# Platienen_schalplan_Backup_2.net
KiCad netlist of a schematic drawn in EAGLE
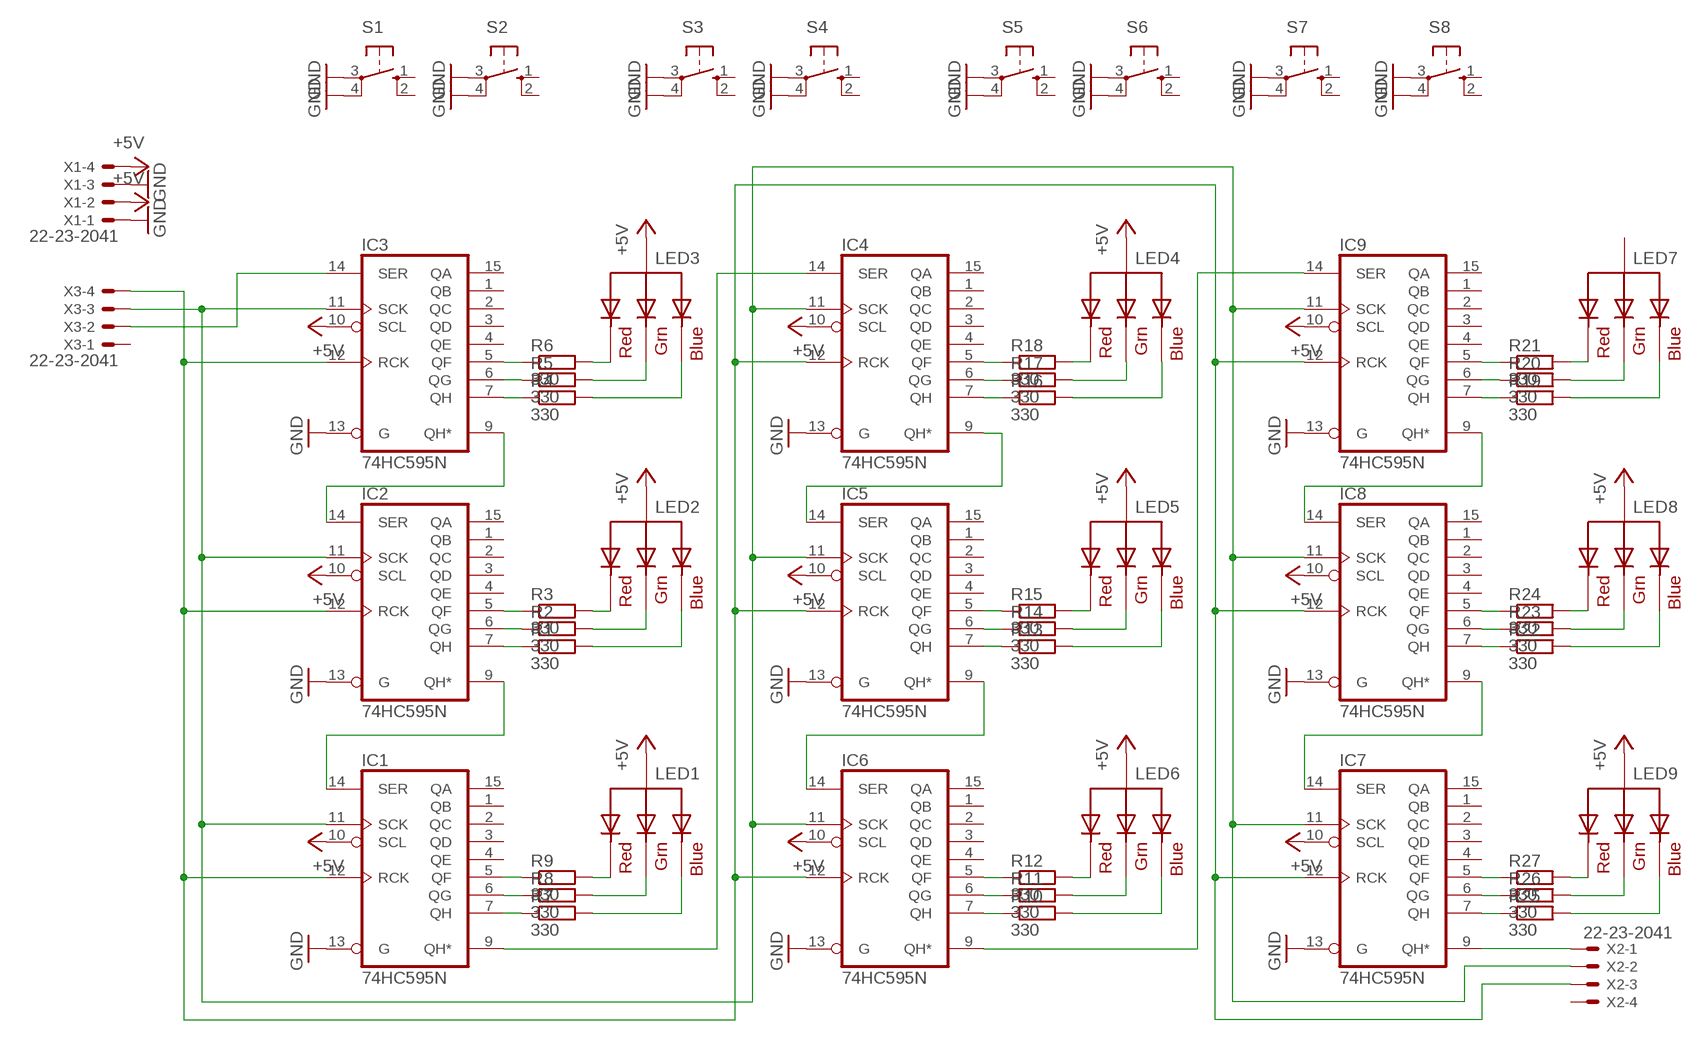
[diagram p0: schematic, sheet 1]

(export (version "E")
  (design (tool "Eeschema 10.0.6"))
  (components
    (comp (ref "IC1")
      (value "74HC595N")
      (footprint "eagle-import:DIL16")
      (libsource (lib "eagle-import") (part "74595NHC"))
    )
    (comp (ref "IC2")
      (value "74HC595N")
      (footprint "eagle-import:DIL16")
      (libsource (lib "eagle-import") (part "74595NHC"))
    )
    (comp (ref "IC3")
      (value "74HC595N")
      (footprint "eagle-import:DIL16")
      (libsource (lib "eagle-import") (part "74595NHC"))
    )
    (comp (ref "IC4")
      (value "74HC595N")
      (footprint "eagle-import:DIL16")
      (libsource (lib "eagle-import") (part "74595NHC"))
    )
    (comp (ref "IC5")
      (value "74HC595N")
      (footprint "eagle-import:DIL16")
      (libsource (lib "eagle-import") (part "74595NHC"))
    )
    (comp (ref "IC6")
      (value "74HC595N")
      (footprint "eagle-import:DIL16")
      (libsource (lib "eagle-import") (part "74595NHC"))
    )
    (comp (ref "IC7")
      (value "74HC595N")
      (footprint "eagle-import:DIL16")
      (libsource (lib "eagle-import") (part "74595NHC"))
    )
    (comp (ref "IC8")
      (value "74HC595N")
      (footprint "eagle-import:DIL16")
      (libsource (lib "eagle-import") (part "74595NHC"))
    )
    (comp (ref "IC9")
      (value "74HC595N")
      (footprint "eagle-import:DIL16")
      (libsource (lib "eagle-import") (part "74595NHC"))
    )
    (comp (ref "LED1")
      (value "RGBLED_CA-5MM")
      (footprint "eagle-import:LED5MMRGB")
      (libsource (lib "eagle-import") (part "RGBLED_CA-5MM"))
    )
    (comp (ref "LED2")
      (value "RGBLED_CA-5MM")
      (footprint "eagle-import:LED5MMRGB")
      (libsource (lib "eagle-import") (part "RGBLED_CA-5MM"))
    )
    (comp (ref "LED3")
      (value "RGBLED_CA-5MM")
      (footprint "eagle-import:LED5MMRGB")
      (libsource (lib "eagle-import") (part "RGBLED_CA-5MM"))
    )
    (comp (ref "LED4")
      (value "RGBLED_CA-5MM")
      (footprint "eagle-import:LED5MMRGB")
      (libsource (lib "eagle-import") (part "RGBLED_CA-5MM"))
    )
    (comp (ref "LED5")
      (value "RGBLED_CA-5MM")
      (footprint "eagle-import:LED5MMRGB")
      (libsource (lib "eagle-import") (part "RGBLED_CA-5MM"))
    )
    (comp (ref "LED6")
      (value "RGBLED_CA-5MM")
      (footprint "eagle-import:LED5MMRGB")
      (libsource (lib "eagle-import") (part "RGBLED_CA-5MM"))
    )
    (comp (ref "LED7")
      (value "RGBLED_CA-5MM")
      (footprint "eagle-import:LED5MMRGB")
      (libsource (lib "eagle-import") (part "RGBLED_CA-5MM"))
    )
    (comp (ref "LED8")
      (value "RGBLED_CA-5MM")
      (footprint "eagle-import:LED5MMRGB")
      (libsource (lib "eagle-import") (part "RGBLED_CA-5MM"))
    )
    (comp (ref "LED9")
      (value "RGBLED_CA-5MM")
      (footprint "eagle-import:LED5MMRGB")
      (libsource (lib "eagle-import") (part "RGBLED_CA-5MM"))
    )
    (comp (ref "R1")
      (value "330")
      (footprint "eagle-import:0204_5")
      (libsource (lib "eagle-import") (part "R-EU_0204/5"))
    )
    (comp (ref "R2")
      (value "330")
      (footprint "eagle-import:0204_5")
      (libsource (lib "eagle-import") (part "R-EU_0204/5"))
    )
    (comp (ref "R3")
      (value "330")
      (footprint "eagle-import:0204_5")
      (libsource (lib "eagle-import") (part "R-EU_0204/5"))
    )
    (comp (ref "R4")
      (value "330")
      (footprint "eagle-import:0204_5")
      (libsource (lib "eagle-import") (part "R-EU_0204/5"))
    )
    (comp (ref "R5")
      (value "330")
      (footprint "eagle-import:0204_5")
      (libsource (lib "eagle-import") (part "R-EU_0204/5"))
    )
    (comp (ref "R6")
      (value "330")
      (footprint "eagle-import:0204_5")
      (libsource (lib "eagle-import") (part "R-EU_0204/5"))
    )
    (comp (ref "R7")
      (value "330")
      (footprint "eagle-import:0204_5")
      (libsource (lib "eagle-import") (part "R-EU_0204/5"))
    )
    (comp (ref "R8")
      (value "330")
      (footprint "eagle-import:0204_5")
      (libsource (lib "eagle-import") (part "R-EU_0204/5"))
    )
    (comp (ref "R9")
      (value "330")
      (footprint "eagle-import:0204_5")
      (libsource (lib "eagle-import") (part "R-EU_0204/5"))
    )
    (comp (ref "R10")
      (value "330")
      (footprint "eagle-import:0204_5")
      (libsource (lib "eagle-import") (part "R-EU_0204/5"))
    )
    (comp (ref "R11")
      (value "330")
      (footprint "eagle-import:0204_5")
      (libsource (lib "eagle-import") (part "R-EU_0204/5"))
    )
    (comp (ref "R12")
      (value "330")
      (footprint "eagle-import:0204_5")
      (libsource (lib "eagle-import") (part "R-EU_0204/5"))
    )
    (comp (ref "R13")
      (value "330")
      (footprint "eagle-import:0204_5")
      (libsource (lib "eagle-import") (part "R-EU_0204/5"))
    )
    (comp (ref "R14")
      (value "330")
      (footprint "eagle-import:0204_5")
      (libsource (lib "eagle-import") (part "R-EU_0204/5"))
    )
    (comp (ref "R15")
      (value "330")
      (footprint "eagle-import:0204_5")
      (libsource (lib "eagle-import") (part "R-EU_0204/5"))
    )
    (comp (ref "R16")
      (value "330")
      (footprint "eagle-import:0204_5")
      (libsource (lib "eagle-import") (part "R-EU_0204/5"))
    )
    (comp (ref "R17")
      (value "330")
      (footprint "eagle-import:0204_5")
      (libsource (lib "eagle-import") (part "R-EU_0204/5"))
    )
    (comp (ref "R18")
      (value "330")
      (footprint "eagle-import:0204_5")
      (libsource (lib "eagle-import") (part "R-EU_0204/5"))
    )
    (comp (ref "R19")
      (value "330")
      (footprint "eagle-import:0204_5")
      (libsource (lib "eagle-import") (part "R-EU_0204/5"))
    )
    (comp (ref "R20")
      (value "330")
      (footprint "eagle-import:0204_5")
      (libsource (lib "eagle-import") (part "R-EU_0204/5"))
    )
    (comp (ref "R21")
      (value "330")
      (footprint "eagle-import:0204_5")
      (libsource (lib "eagle-import") (part "R-EU_0204/5"))
    )
    (comp (ref "R22")
      (value "330")
      (footprint "eagle-import:0204_5")
      (libsource (lib "eagle-import") (part "R-EU_0204/5"))
    )
    (comp (ref "R23")
      (value "330")
      (footprint "eagle-import:0204_5")
      (libsource (lib "eagle-import") (part "R-EU_0204/5"))
    )
    (comp (ref "R24")
      (value "330")
      (footprint "eagle-import:0204_5")
      (libsource (lib "eagle-import") (part "R-EU_0204/5"))
    )
    (comp (ref "R25")
      (value "330")
      (footprint "eagle-import:0204_5")
      (libsource (lib "eagle-import") (part "R-EU_0204/5"))
    )
    (comp (ref "R26")
      (value "330")
      (footprint "eagle-import:0204_5")
      (libsource (lib "eagle-import") (part "R-EU_0204/5"))
    )
    (comp (ref "R27")
      (value "330")
      (footprint "eagle-import:0204_5")
      (libsource (lib "eagle-import") (part "R-EU_0204/5"))
    )
    (comp (ref "S1")
      (value "10-XX")
      (footprint "eagle-import:B3F-10XX")
      (fields (field (name "MPN") "B3F-1000"))
      (libsource (lib "eagle-import") (part "10-XX"))
    )
    (comp (ref "S2")
      (value "10-XX")
      (footprint "eagle-import:B3F-10XX")
      (fields (field (name "MPN") "B3F-1000"))
      (libsource (lib "eagle-import") (part "10-XX"))
    )
    (comp (ref "S3")
      (value "10-XX")
      (footprint "eagle-import:B3F-10XX")
      (fields (field (name "MPN") "B3F-1000"))
      (libsource (lib "eagle-import") (part "10-XX"))
    )
    (comp (ref "S4")
      (value "10-XX")
      (footprint "eagle-import:B3F-10XX")
      (fields (field (name "MPN") "B3F-1000"))
      (libsource (lib "eagle-import") (part "10-XX"))
    )
    (comp (ref "S5")
      (value "10-XX")
      (footprint "eagle-import:B3F-10XX")
      (fields (field (name "MPN") "B3F-1000"))
      (libsource (lib "eagle-import") (part "10-XX"))
    )
    (comp (ref "S6")
      (value "10-XX")
      (footprint "eagle-import:B3F-10XX")
      (fields (field (name "MPN") "B3F-1000"))
      (libsource (lib "eagle-import") (part "10-XX"))
    )
    (comp (ref "S7")
      (value "10-XX")
      (footprint "eagle-import:B3F-10XX")
      (fields (field (name "MPN") "B3F-1000"))
      (libsource (lib "eagle-import") (part "10-XX"))
    )
    (comp (ref "S8")
      (value "10-XX")
      (footprint "eagle-import:B3F-10XX")
      (fields (field (name "MPN") "B3F-1000"))
      (libsource (lib "eagle-import") (part "10-XX"))
    )
    (comp (ref "X1")
      (value "22-23-2041")
      (footprint "eagle-import:22-23-2041")
      (fields (field (name "MF") "MOLEX"))
      (libsource (lib "eagle-import") (part "22-23-2041"))
    )
    (comp (ref "X2")
      (value "22-23-2041")
      (footprint "eagle-import:22-23-2041")
      (fields (field (name "MF") "MOLEX"))
      (libsource (lib "eagle-import") (part "22-23-2041"))
    )
    (comp (ref "X3")
      (value "22-23-2041")
      (footprint "eagle-import:22-23-2041")
      (fields (field (name "MF") "MOLEX"))
      (libsource (lib "eagle-import") (part "22-23-2041"))
    )
  )
  (nets
    (net (code "1") (name "+5V") (class "Default")
      (node (ref "IC1") (pin "10") (pinfunction "SCL_10") (pintype "input"))
      (node (ref "IC2") (pin "10") (pinfunction "SCL_10") (pintype "input"))
      (node (ref "IC3") (pin "10") (pinfunction "SCL_10") (pintype "input"))
      (node (ref "IC4") (pin "10") (pinfunction "SCL_10") (pintype "input"))
      (node (ref "IC5") (pin "10") (pinfunction "SCL_10") (pintype "input"))
      (node (ref "IC6") (pin "10") (pinfunction "SCL_10") (pintype "input"))
      (node (ref "IC7") (pin "10") (pinfunction "SCL_10") (pintype "input"))
      (node (ref "IC8") (pin "10") (pinfunction "SCL_10") (pintype "input"))
      (node (ref "IC9") (pin "10") (pinfunction "SCL_10") (pintype "input"))
      (node (ref "LED1") (pin "2") (pinfunction "VCC_2") (pintype "bidirectional"))
      (node (ref "LED2") (pin "2") (pinfunction "VCC_2") (pintype "bidirectional"))
      (node (ref "LED3") (pin "2") (pinfunction "VCC_2") (pintype "bidirectional"))
      (node (ref "LED4") (pin "2") (pinfunction "VCC_2") (pintype "bidirectional"))
      (node (ref "LED5") (pin "2") (pinfunction "VCC_2") (pintype "bidirectional"))
      (node (ref "LED6") (pin "2") (pinfunction "VCC_2") (pintype "bidirectional"))
      (node (ref "LED8") (pin "2") (pinfunction "VCC_2") (pintype "bidirectional"))
      (node (ref "LED9") (pin "2") (pinfunction "VCC_2") (pintype "bidirectional"))
      (node (ref "X1") (pin "2") (pinfunction "S_2") (pintype "passive"))
      (node (ref "X1") (pin "4") (pinfunction "S_4") (pintype "passive"))
    )
    (net (code "2") (name "GND") (class "Default")
      (node (ref "IC1") (pin "13") (pinfunction "G_13") (pintype "input"))
      (node (ref "IC2") (pin "13") (pinfunction "G_13") (pintype "input"))
      (node (ref "IC3") (pin "13") (pinfunction "G_13") (pintype "input"))
      (node (ref "IC4") (pin "13") (pinfunction "G_13") (pintype "input"))
      (node (ref "IC5") (pin "13") (pinfunction "G_13") (pintype "input"))
      (node (ref "IC6") (pin "13") (pinfunction "G_13") (pintype "input"))
      (node (ref "IC7") (pin "13") (pinfunction "G_13") (pintype "input"))
      (node (ref "IC8") (pin "13") (pinfunction "G_13") (pintype "input"))
      (node (ref "IC9") (pin "13") (pinfunction "G_13") (pintype "input"))
      (node (ref "S1") (pin "3") (pinfunction "P_3") (pintype "passive"))
      (node (ref "S1") (pin "4") (pinfunction "P1_4") (pintype "passive"))
      (node (ref "S2") (pin "3") (pinfunction "P_3") (pintype "passive"))
      (node (ref "S2") (pin "4") (pinfunction "P1_4") (pintype "passive"))
      (node (ref "S3") (pin "3") (pinfunction "P_3") (pintype "passive"))
      (node (ref "S3") (pin "4") (pinfunction "P1_4") (pintype "passive"))
      (node (ref "S4") (pin "3") (pinfunction "P_3") (pintype "passive"))
      (node (ref "S4") (pin "4") (pinfunction "P1_4") (pintype "passive"))
      (node (ref "S5") (pin "3") (pinfunction "P_3") (pintype "passive"))
      (node (ref "S5") (pin "4") (pinfunction "P1_4") (pintype "passive"))
      (node (ref "S6") (pin "3") (pinfunction "P_3") (pintype "passive"))
      (node (ref "S6") (pin "4") (pinfunction "P1_4") (pintype "passive"))
      (node (ref "S7") (pin "3") (pinfunction "P_3") (pintype "passive"))
      (node (ref "S7") (pin "4") (pinfunction "P1_4") (pintype "passive"))
      (node (ref "S8") (pin "3") (pinfunction "P_3") (pintype "passive"))
      (node (ref "S8") (pin "4") (pinfunction "P1_4") (pintype "passive"))
      (node (ref "X1") (pin "1") (pinfunction "S_1") (pintype "passive"))
      (node (ref "X1") (pin "3") (pinfunction "S_3") (pintype "passive"))
    )
    (net (code "3") (name "Net-(IC1A-QF)") (class "Default")
      (node (ref "IC1") (pin "5") (pinfunction "QF_5") (pintype "tri_state"))
      (node (ref "R9") (pin "1") (pinfunction "1_1") (pintype "passive"))
    )
    (net (code "4") (name "Net-(IC1A-QG)") (class "Default")
      (node (ref "IC1") (pin "6") (pinfunction "QG_6") (pintype "tri_state"))
      (node (ref "R8") (pin "1") (pinfunction "1_1") (pintype "passive"))
    )
    (net (code "5") (name "Net-(IC1A-QH)") (class "Default")
      (node (ref "IC1") (pin "7") (pinfunction "QH_7") (pintype "tri_state"))
      (node (ref "R7") (pin "1") (pinfunction "1_1") (pintype "passive"))
    )
    (net (code "6") (name "Net-(IC1A-QH*)") (class "Default")
      (node (ref "IC1") (pin "9") (pinfunction "QH*_9") (pintype "tri_state"))
      (node (ref "IC4") (pin "14") (pinfunction "SER_14") (pintype "input"))
    )
    (net (code "7") (name "Net-(IC1A-RCK)") (class "Default")
      (node (ref "IC1") (pin "12") (pinfunction "RCK_12") (pintype "input"))
      (node (ref "IC2") (pin "12") (pinfunction "RCK_12") (pintype "input"))
      (node (ref "IC3") (pin "12") (pinfunction "RCK_12") (pintype "input"))
      (node (ref "IC4") (pin "12") (pinfunction "RCK_12") (pintype "input"))
      (node (ref "IC5") (pin "12") (pinfunction "RCK_12") (pintype "input"))
      (node (ref "IC6") (pin "12") (pinfunction "RCK_12") (pintype "input"))
      (node (ref "IC7") (pin "12") (pinfunction "RCK_12") (pintype "input"))
      (node (ref "IC8") (pin "12") (pinfunction "RCK_12") (pintype "input"))
      (node (ref "IC9") (pin "12") (pinfunction "RCK_12") (pintype "input"))
      (node (ref "X2") (pin "3") (pinfunction "S_3") (pintype "passive"))
      (node (ref "X3") (pin "4") (pinfunction "S_4") (pintype "passive"))
    )
    (net (code "8") (name "Net-(IC1A-SCK)") (class "Default")
      (node (ref "IC1") (pin "11") (pinfunction "SCK_11") (pintype "input"))
      (node (ref "IC2") (pin "11") (pinfunction "SCK_11") (pintype "input"))
      (node (ref "IC3") (pin "11") (pinfunction "SCK_11") (pintype "input"))
      (node (ref "IC4") (pin "11") (pinfunction "SCK_11") (pintype "input"))
      (node (ref "IC5") (pin "11") (pinfunction "SCK_11") (pintype "input"))
      (node (ref "IC6") (pin "11") (pinfunction "SCK_11") (pintype "input"))
      (node (ref "IC7") (pin "11") (pinfunction "SCK_11") (pintype "input"))
      (node (ref "IC8") (pin "11") (pinfunction "SCK_11") (pintype "input"))
      (node (ref "IC9") (pin "11") (pinfunction "SCK_11") (pintype "input"))
      (node (ref "X2") (pin "2") (pinfunction "S_2") (pintype "passive"))
      (node (ref "X3") (pin "3") (pinfunction "S_3") (pintype "passive"))
    )
    (net (code "9") (name "Net-(IC1A-SER)") (class "Default")
      (node (ref "IC1") (pin "14") (pinfunction "SER_14") (pintype "input"))
      (node (ref "IC2") (pin "9") (pinfunction "QH*_9") (pintype "tri_state"))
    )
    (net (code "10") (name "Net-(IC2A-QF)") (class "Default")
      (node (ref "IC2") (pin "5") (pinfunction "QF_5") (pintype "tri_state"))
      (node (ref "R3") (pin "1") (pinfunction "1_1") (pintype "passive"))
    )
    (net (code "11") (name "Net-(IC2A-QG)") (class "Default")
      (node (ref "IC2") (pin "6") (pinfunction "QG_6") (pintype "tri_state"))
      (node (ref "R2") (pin "1") (pinfunction "1_1") (pintype "passive"))
    )
    (net (code "12") (name "Net-(IC2A-QH)") (class "Default")
      (node (ref "IC2") (pin "7") (pinfunction "QH_7") (pintype "tri_state"))
      (node (ref "R1") (pin "1") (pinfunction "1_1") (pintype "passive"))
    )
    (net (code "13") (name "Net-(IC2A-SER)") (class "Default")
      (node (ref "IC2") (pin "14") (pinfunction "SER_14") (pintype "input"))
      (node (ref "IC3") (pin "9") (pinfunction "QH*_9") (pintype "tri_state"))
    )
    (net (code "14") (name "Net-(IC3A-QF)") (class "Default")
      (node (ref "IC3") (pin "5") (pinfunction "QF_5") (pintype "tri_state"))
      (node (ref "R6") (pin "1") (pinfunction "1_1") (pintype "passive"))
    )
    (net (code "15") (name "Net-(IC3A-QG)") (class "Default")
      (node (ref "IC3") (pin "6") (pinfunction "QG_6") (pintype "tri_state"))
      (node (ref "R5") (pin "1") (pinfunction "1_1") (pintype "passive"))
    )
    (net (code "16") (name "Net-(IC3A-QH)") (class "Default")
      (node (ref "IC3") (pin "7") (pinfunction "QH_7") (pintype "tri_state"))
      (node (ref "R4") (pin "1") (pinfunction "1_1") (pintype "passive"))
    )
    (net (code "17") (name "Net-(IC3A-SER)") (class "Default")
      (node (ref "IC3") (pin "14") (pinfunction "SER_14") (pintype "input"))
      (node (ref "X3") (pin "2") (pinfunction "S_2") (pintype "passive"))
    )
    (net (code "18") (name "Net-(IC4A-QF)") (class "Default")
      (node (ref "IC4") (pin "5") (pinfunction "QF_5") (pintype "tri_state"))
      (node (ref "R18") (pin "1") (pinfunction "1_1") (pintype "passive"))
    )
    (net (code "19") (name "Net-(IC4A-QG)") (class "Default")
      (node (ref "IC4") (pin "6") (pinfunction "QG_6") (pintype "tri_state"))
      (node (ref "R17") (pin "1") (pinfunction "1_1") (pintype "passive"))
    )
    (net (code "20") (name "Net-(IC4A-QH)") (class "Default")
      (node (ref "IC4") (pin "7") (pinfunction "QH_7") (pintype "tri_state"))
      (node (ref "R16") (pin "1") (pinfunction "1_1") (pintype "passive"))
    )
    (net (code "21") (name "Net-(IC4A-QH*)") (class "Default")
      (node (ref "IC4") (pin "9") (pinfunction "QH*_9") (pintype "tri_state"))
      (node (ref "IC5") (pin "14") (pinfunction "SER_14") (pintype "input"))
    )
    (net (code "22") (name "Net-(IC5A-QF)") (class "Default")
      (node (ref "IC5") (pin "5") (pinfunction "QF_5") (pintype "tri_state"))
      (node (ref "R15") (pin "1") (pinfunction "1_1") (pintype "passive"))
    )
    (net (code "23") (name "Net-(IC5A-QG)") (class "Default")
      (node (ref "IC5") (pin "6") (pinfunction "QG_6") (pintype "tri_state"))
      (node (ref "R14") (pin "1") (pinfunction "1_1") (pintype "passive"))
    )
    (net (code "24") (name "Net-(IC5A-QH)") (class "Default")
      (node (ref "IC5") (pin "7") (pinfunction "QH_7") (pintype "tri_state"))
      (node (ref "R13") (pin "1") (pinfunction "1_1") (pintype "passive"))
    )
    (net (code "25") (name "Net-(IC5A-QH*)") (class "Default")
      (node (ref "IC5") (pin "9") (pinfunction "QH*_9") (pintype "tri_state"))
      (node (ref "IC6") (pin "14") (pinfunction "SER_14") (pintype "input"))
    )
    (net (code "26") (name "Net-(IC6A-QF)") (class "Default")
      (node (ref "IC6") (pin "5") (pinfunction "QF_5") (pintype "tri_state"))
      (node (ref "R12") (pin "1") (pinfunction "1_1") (pintype "passive"))
    )
    (net (code "27") (name "Net-(IC6A-QG)") (class "Default")
      (node (ref "IC6") (pin "6") (pinfunction "QG_6") (pintype "tri_state"))
      (node (ref "R11") (pin "1") (pinfunction "1_1") (pintype "passive"))
    )
    (net (code "28") (name "Net-(IC6A-QH)") (class "Default")
      (node (ref "IC6") (pin "7") (pinfunction "QH_7") (pintype "tri_state"))
      (node (ref "R10") (pin "1") (pinfunction "1_1") (pintype "passive"))
    )
    (net (code "29") (name "Net-(IC6A-QH*)") (class "Default")
      (node (ref "IC6") (pin "9") (pinfunction "QH*_9") (pintype "tri_state"))
      (node (ref "IC9") (pin "14") (pinfunction "SER_14") (pintype "input"))
    )
    (net (code "30") (name "Net-(IC7A-QF)") (class "Default")
      (node (ref "IC7") (pin "5") (pinfunction "QF_5") (pintype "tri_state"))
      (node (ref "R27") (pin "1") (pinfunction "1_1") (pintype "passive"))
    )
    (net (code "31") (name "Net-(IC7A-QG)") (class "Default")
      (node (ref "IC7") (pin "6") (pinfunction "QG_6") (pintype "tri_state"))
      (node (ref "R26") (pin "1") (pinfunction "1_1") (pintype "passive"))
    )
    (net (code "32") (name "Net-(IC7A-QH)") (class "Default")
      (node (ref "IC7") (pin "7") (pinfunction "QH_7") (pintype "tri_state"))
      (node (ref "R25") (pin "1") (pinfunction "1_1") (pintype "passive"))
    )
    (net (code "33") (name "Net-(IC7A-QH*)") (class "Default")
      (node (ref "IC7") (pin "9") (pinfunction "QH*_9") (pintype "tri_state"))
      (node (ref "X2") (pin "1") (pinfunction "S_1") (pintype "passive"))
    )
    (net (code "34") (name "Net-(IC7A-SER)") (class "Default")
      (node (ref "IC7") (pin "14") (pinfunction "SER_14") (pintype "input"))
      (node (ref "IC8") (pin "9") (pinfunction "QH*_9") (pintype "tri_state"))
    )
    (net (code "35") (name "Net-(IC8A-QF)") (class "Default")
      (node (ref "IC8") (pin "5") (pinfunction "QF_5") (pintype "tri_state"))
      (node (ref "R24") (pin "1") (pinfunction "1_1") (pintype "passive"))
    )
    (net (code "36") (name "Net-(IC8A-QG)") (class "Default")
      (node (ref "IC8") (pin "6") (pinfunction "QG_6") (pintype "tri_state"))
      (node (ref "R23") (pin "1") (pinfunction "1_1") (pintype "passive"))
    )
    (net (code "37") (name "Net-(IC8A-QH)") (class "Default")
      (node (ref "IC8") (pin "7") (pinfunction "QH_7") (pintype "tri_state"))
      (node (ref "R22") (pin "1") (pinfunction "1_1") (pintype "passive"))
    )
    (net (code "38") (name "Net-(IC8A-SER)") (class "Default")
      (node (ref "IC8") (pin "14") (pinfunction "SER_14") (pintype "input"))
      (node (ref "IC9") (pin "9") (pinfunction "QH*_9") (pintype "tri_state"))
    )
    (net (code "39") (name "Net-(IC9A-QF)") (class "Default")
      (node (ref "IC9") (pin "5") (pinfunction "QF_5") (pintype "tri_state"))
      (node (ref "R21") (pin "1") (pinfunction "1_1") (pintype "passive"))
    )
    (net (code "40") (name "Net-(IC9A-QG)") (class "Default")
      (node (ref "IC9") (pin "6") (pinfunction "QG_6") (pintype "tri_state"))
      (node (ref "R20") (pin "1") (pinfunction "1_1") (pintype "passive"))
    )
    (net (code "41") (name "Net-(IC9A-QH)") (class "Default")
      (node (ref "IC9") (pin "7") (pinfunction "QH_7") (pintype "tri_state"))
      (node (ref "R19") (pin "1") (pinfunction "1_1") (pintype "passive"))
    )
    (net (code "42") (name "Net-(LED1-BLUE)") (class "Default")
      (node (ref "LED1") (pin "4") (pinfunction "BLUE_4") (pintype "bidirectional"))
      (node (ref "R7") (pin "2") (pinfunction "2_2") (pintype "passive"))
    )
    (net (code "43") (name "Net-(LED1-GREEN)") (class "Default")
      (node (ref "LED1") (pin "3") (pinfunction "GREEN_3") (pintype "bidirectional"))
      (node (ref "R8") (pin "2") (pinfunction "2_2") (pintype "passive"))
    )
    (net (code "44") (name "Net-(LED1-RED)") (class "Default")
      (node (ref "LED1") (pin "1") (pinfunction "RED_1") (pintype "bidirectional"))
      (node (ref "R9") (pin "2") (pinfunction "2_2") (pintype "passive"))
    )
    (net (code "45") (name "Net-(LED2-BLUE)") (class "Default")
      (node (ref "LED2") (pin "4") (pinfunction "BLUE_4") (pintype "bidirectional"))
      (node (ref "R1") (pin "2") (pinfunction "2_2") (pintype "passive"))
    )
    (net (code "46") (name "Net-(LED2-GREEN)") (class "Default")
      (node (ref "LED2") (pin "3") (pinfunction "GREEN_3") (pintype "bidirectional"))
      (node (ref "R2") (pin "2") (pinfunction "2_2") (pintype "passive"))
    )
    (net (code "47") (name "Net-(LED2-RED)") (class "Default")
      (node (ref "LED2") (pin "1") (pinfunction "RED_1") (pintype "bidirectional"))
      (node (ref "R3") (pin "2") (pinfunction "2_2") (pintype "passive"))
    )
    (net (code "48") (name "Net-(LED3-BLUE)") (class "Default")
      (node (ref "LED3") (pin "4") (pinfunction "BLUE_4") (pintype "bidirectional"))
      (node (ref "R4") (pin "2") (pinfunction "2_2") (pintype "passive"))
    )
    (net (code "49") (name "Net-(LED3-GREEN)") (class "Default")
      (node (ref "LED3") (pin "3") (pinfunction "GREEN_3") (pintype "bidirectional"))
      (node (ref "R5") (pin "2") (pinfunction "2_2") (pintype "passive"))
    )
    (net (code "50") (name "Net-(LED3-RED)") (class "Default")
      (node (ref "LED3") (pin "1") (pinfunction "RED_1") (pintype "bidirectional"))
      (node (ref "R6") (pin "2") (pinfunction "2_2") (pintype "passive"))
    )
    (net (code "51") (name "Net-(LED4-BLUE)") (class "Default")
      (node (ref "LED4") (pin "4") (pinfunction "BLUE_4") (pintype "bidirectional"))
      (node (ref "R16") (pin "2") (pinfunction "2_2") (pintype "passive"))
    )
    (net (code "52") (name "Net-(LED4-GREEN)") (class "Default")
      (node (ref "LED4") (pin "3") (pinfunction "GREEN_3") (pintype "bidirectional"))
      (node (ref "R17") (pin "2") (pinfunction "2_2") (pintype "passive"))
    )
    (net (code "53") (name "Net-(LED4-RED)") (class "Default")
      (node (ref "LED4") (pin "1") (pinfunction "RED_1") (pintype "bidirectional"))
      (node (ref "R18") (pin "2") (pinfunction "2_2") (pintype "passive"))
    )
    (net (code "54") (name "Net-(LED5-BLUE)") (class "Default")
      (node (ref "LED5") (pin "4") (pinfunction "BLUE_4") (pintype "bidirectional"))
      (node (ref "R13") (pin "2") (pinfunction "2_2") (pintype "passive"))
    )
    (net (code "55") (name "Net-(LED5-GREEN)") (class "Default")
      (node (ref "LED5") (pin "3") (pinfunction "GREEN_3") (pintype "bidirectional"))
      (node (ref "R14") (pin "2") (pinfunction "2_2") (pintype "passive"))
    )
    (net (code "56") (name "Net-(LED5-RED)") (class "Default")
      (node (ref "LED5") (pin "1") (pinfunction "RED_1") (pintype "bidirectional"))
      (node (ref "R15") (pin "2") (pinfunction "2_2") (pintype "passive"))
    )
    (net (code "57") (name "Net-(LED6-BLUE)") (class "Default")
      (node (ref "LED6") (pin "4") (pinfunction "BLUE_4") (pintype "bidirectional"))
      (node (ref "R10") (pin "2") (pinfunction "2_2") (pintype "passive"))
    )
    (net (code "58") (name "Net-(LED6-GREEN)") (class "Default")
      (node (ref "LED6") (pin "3") (pinfunction "GREEN_3") (pintype "bidirectional"))
      (node (ref "R11") (pin "2") (pinfunction "2_2") (pintype "passive"))
    )
    (net (code "59") (name "Net-(LED6-RED)") (class "Default")
      (node (ref "LED6") (pin "1") (pinfunction "RED_1") (pintype "bidirectional"))
      (node (ref "R12") (pin "2") (pinfunction "2_2") (pintype "passive"))
    )
    (net (code "60") (name "Net-(LED7-BLUE)") (class "Default")
      (node (ref "LED7") (pin "4") (pinfunction "BLUE_4") (pintype "bidirectional"))
      (node (ref "R19") (pin "2") (pinfunction "2_2") (pintype "passive"))
    )
    (net (code "61") (name "Net-(LED7-GREEN)") (class "Default")
      (node (ref "LED7") (pin "3") (pinfunction "GREEN_3") (pintype "bidirectional"))
      (node (ref "R20") (pin "2") (pinfunction "2_2") (pintype "passive"))
    )
    (net (code "62") (name "Net-(LED7-RED)") (class "Default")
      (node (ref "LED7") (pin "1") (pinfunction "RED_1") (pintype "bidirectional"))
      (node (ref "R21") (pin "2") (pinfunction "2_2") (pintype "passive"))
    )
    (net (code "63") (name "Net-(LED8-BLUE)") (class "Default")
      (node (ref "LED8") (pin "4") (pinfunction "BLUE_4") (pintype "bidirectional"))
      (node (ref "R22") (pin "2") (pinfunction "2_2") (pintype "passive"))
    )
    (net (code "64") (name "Net-(LED8-GREEN)") (class "Default")
      (node (ref "LED8") (pin "3") (pinfunction "GREEN_3") (pintype "bidirectional"))
      (node (ref "R23") (pin "2") (pinfunction "2_2") (pintype "passive"))
    )
    (net (code "65") (name "Net-(LED8-RED)") (class "Default")
      (node (ref "LED8") (pin "1") (pinfunction "RED_1") (pintype "bidirectional"))
      (node (ref "R24") (pin "2") (pinfunction "2_2") (pintype "passive"))
    )
    (net (code "66") (name "Net-(LED9-BLUE)") (class "Default")
      (node (ref "LED9") (pin "4") (pinfunction "BLUE_4") (pintype "bidirectional"))
      (node (ref "R25") (pin "2") (pinfunction "2_2") (pintype "passive"))
    )
    (net (code "67") (name "Net-(LED9-GREEN)") (class "Default")
      (node (ref "LED9") (pin "3") (pinfunction "GREEN_3") (pintype "bidirectional"))
      (node (ref "R26") (pin "2") (pinfunction "2_2") (pintype "passive"))
    )
    (net (code "68") (name "Net-(LED9-RED)") (class "Default")
      (node (ref "LED9") (pin "1") (pinfunction "RED_1") (pintype "bidirectional"))
      (node (ref "R27") (pin "2") (pinfunction "2_2") (pintype "passive"))
    )
    (net (code "69") (name "unconnected-(IC1A-QA-Pad15)") (class "Default")
      (node (ref "IC1") (pin "15") (pinfunction "QA_15") (pintype "tri_state"))
    )
    (net (code "70") (name "unconnected-(IC1A-QB-Pad1)") (class "Default")
      (node (ref "IC1") (pin "1") (pinfunction "QB_1") (pintype "tri_state"))
    )
    (net (code "71") (name "unconnected-(IC1A-QC-Pad2)") (class "Default")
      (node (ref "IC1") (pin "2") (pinfunction "QC_2") (pintype "tri_state"))
    )
    (net (code "72") (name "unconnected-(IC1A-QD-Pad3)") (class "Default")
      (node (ref "IC1") (pin "3") (pinfunction "QD_3") (pintype "tri_state"))
    )
    (net (code "73") (name "unconnected-(IC1A-QE-Pad4)") (class "Default")
      (node (ref "IC1") (pin "4") (pinfunction "QE_4") (pintype "tri_state"))
    )
    (net (code "74") (name "unconnected-(IC2A-QA-Pad15)") (class "Default")
      (node (ref "IC2") (pin "15") (pinfunction "QA_15") (pintype "tri_state"))
    )
    (net (code "75") (name "unconnected-(IC2A-QB-Pad1)") (class "Default")
      (node (ref "IC2") (pin "1") (pinfunction "QB_1") (pintype "tri_state"))
    )
    (net (code "76") (name "unconnected-(IC2A-QC-Pad2)") (class "Default")
      (node (ref "IC2") (pin "2") (pinfunction "QC_2") (pintype "tri_state"))
    )
    (net (code "77") (name "unconnected-(IC2A-QD-Pad3)") (class "Default")
      (node (ref "IC2") (pin "3") (pinfunction "QD_3") (pintype "tri_state"))
    )
    (net (code "78") (name "unconnected-(IC2A-QE-Pad4)") (class "Default")
      (node (ref "IC2") (pin "4") (pinfunction "QE_4") (pintype "tri_state"))
    )
    (net (code "79") (name "unconnected-(IC3A-QA-Pad15)") (class "Default")
      (node (ref "IC3") (pin "15") (pinfunction "QA_15") (pintype "tri_state"))
    )
    (net (code "80") (name "unconnected-(IC3A-QB-Pad1)") (class "Default")
      (node (ref "IC3") (pin "1") (pinfunction "QB_1") (pintype "tri_state"))
    )
    (net (code "81") (name "unconnected-(IC3A-QC-Pad2)") (class "Default")
      (node (ref "IC3") (pin "2") (pinfunction "QC_2") (pintype "tri_state"))
    )
    (net (code "82") (name "unconnected-(IC3A-QD-Pad3)") (class "Default")
      (node (ref "IC3") (pin "3") (pinfunction "QD_3") (pintype "tri_state"))
    )
    (net (code "83") (name "unconnected-(IC3A-QE-Pad4)") (class "Default")
      (node (ref "IC3") (pin "4") (pinfunction "QE_4") (pintype "tri_state"))
    )
    (net (code "84") (name "unconnected-(IC4A-QA-Pad15)") (class "Default")
      (node (ref "IC4") (pin "15") (pinfunction "QA_15") (pintype "tri_state"))
    )
    (net (code "85") (name "unconnected-(IC4A-QB-Pad1)") (class "Default")
      (node (ref "IC4") (pin "1") (pinfunction "QB_1") (pintype "tri_state"))
    )
    (net (code "86") (name "unconnected-(IC4A-QC-Pad2)") (class "Default")
      (node (ref "IC4") (pin "2") (pinfunction "QC_2") (pintype "tri_state"))
    )
    (net (code "87") (name "unconnected-(IC4A-QD-Pad3)") (class "Default")
      (node (ref "IC4") (pin "3") (pinfunction "QD_3") (pintype "tri_state"))
    )
    (net (code "88") (name "unconnected-(IC4A-QE-Pad4)") (class "Default")
      (node (ref "IC4") (pin "4") (pinfunction "QE_4") (pintype "tri_state"))
    )
    (net (code "89") (name "unconnected-(IC5A-QA-Pad15)") (class "Default")
      (node (ref "IC5") (pin "15") (pinfunction "QA_15") (pintype "tri_state"))
    )
    (net (code "90") (name "unconnected-(IC5A-QB-Pad1)") (class "Default")
      (node (ref "IC5") (pin "1") (pinfunction "QB_1") (pintype "tri_state"))
    )
    (net (code "91") (name "unconnected-(IC5A-QC-Pad2)") (class "Default")
      (node (ref "IC5") (pin "2") (pinfunction "QC_2") (pintype "tri_state"))
    )
    (net (code "92") (name "unconnected-(IC5A-QD-Pad3)") (class "Default")
      (node (ref "IC5") (pin "3") (pinfunction "QD_3") (pintype "tri_state"))
    )
    (net (code "93") (name "unconnected-(IC5A-QE-Pad4)") (class "Default")
      (node (ref "IC5") (pin "4") (pinfunction "QE_4") (pintype "tri_state"))
    )
    (net (code "94") (name "unconnected-(IC6A-QA-Pad15)") (class "Default")
      (node (ref "IC6") (pin "15") (pinfunction "QA_15") (pintype "tri_state"))
    )
    (net (code "95") (name "unconnected-(IC6A-QB-Pad1)") (class "Default")
      (node (ref "IC6") (pin "1") (pinfunction "QB_1") (pintype "tri_state"))
    )
    (net (code "96") (name "unconnected-(IC6A-QC-Pad2)") (class "Default")
      (node (ref "IC6") (pin "2") (pinfunction "QC_2") (pintype "tri_state"))
    )
    (net (code "97") (name "unconnected-(IC6A-QD-Pad3)") (class "Default")
      (node (ref "IC6") (pin "3") (pinfunction "QD_3") (pintype "tri_state"))
    )
    (net (code "98") (name "unconnected-(IC6A-QE-Pad4)") (class "Default")
      (node (ref "IC6") (pin "4") (pinfunction "QE_4") (pintype "tri_state"))
    )
    (net (code "99") (name "unconnected-(IC7A-QA-Pad15)") (class "Default")
      (node (ref "IC7") (pin "15") (pinfunction "QA_15") (pintype "tri_state"))
    )
    (net (code "100") (name "unconnected-(IC7A-QB-Pad1)") (class "Default")
      (node (ref "IC7") (pin "1") (pinfunction "QB_1") (pintype "tri_state"))
    )
    (net (code "101") (name "unconnected-(IC7A-QC-Pad2)") (class "Default")
      (node (ref "IC7") (pin "2") (pinfunction "QC_2") (pintype "tri_state"))
    )
    (net (code "102") (name "unconnected-(IC7A-QD-Pad3)") (class "Default")
      (node (ref "IC7") (pin "3") (pinfunction "QD_3") (pintype "tri_state"))
    )
    (net (code "103") (name "unconnected-(IC7A-QE-Pad4)") (class "Default")
      (node (ref "IC7") (pin "4") (pinfunction "QE_4") (pintype "tri_state"))
    )
    (net (code "104") (name "unconnected-(IC8A-QA-Pad15)") (class "Default")
      (node (ref "IC8") (pin "15") (pinfunction "QA_15") (pintype "tri_state"))
    )
    (net (code "105") (name "unconnected-(IC8A-QB-Pad1)") (class "Default")
      (node (ref "IC8") (pin "1") (pinfunction "QB_1") (pintype "tri_state"))
    )
    (net (code "106") (name "unconnected-(IC8A-QC-Pad2)") (class "Default")
      (node (ref "IC8") (pin "2") (pinfunction "QC_2") (pintype "tri_state"))
    )
    (net (code "107") (name "unconnected-(IC8A-QD-Pad3)") (class "Default")
      (node (ref "IC8") (pin "3") (pinfunction "QD_3") (pintype "tri_state"))
    )
    (net (code "108") (name "unconnected-(IC8A-QE-Pad4)") (class "Default")
      (node (ref "IC8") (pin "4") (pinfunction "QE_4") (pintype "tri_state"))
    )
    (net (code "109") (name "unconnected-(IC9A-QA-Pad15)") (class "Default")
      (node (ref "IC9") (pin "15") (pinfunction "QA_15") (pintype "tri_state"))
    )
    (net (code "110") (name "unconnected-(IC9A-QB-Pad1)") (class "Default")
      (node (ref "IC9") (pin "1") (pinfunction "QB_1") (pintype "tri_state"))
    )
    (net (code "111") (name "unconnected-(IC9A-QC-Pad2)") (class "Default")
      (node (ref "IC9") (pin "2") (pinfunction "QC_2") (pintype "tri_state"))
    )
    (net (code "112") (name "unconnected-(IC9A-QD-Pad3)") (class "Default")
      (node (ref "IC9") (pin "3") (pinfunction "QD_3") (pintype "tri_state"))
    )
    (net (code "113") (name "unconnected-(IC9A-QE-Pad4)") (class "Default")
      (node (ref "IC9") (pin "4") (pinfunction "QE_4") (pintype "tri_state"))
    )
    (net (code "114") (name "unconnected-(LED7-VCC-Pad2)") (class "Default")
      (node (ref "LED7") (pin "2") (pinfunction "VCC_2") (pintype "bidirectional"))
    )
    (net (code "115") (name "unconnected-(S1-S-Pad1)") (class "Default")
      (node (ref "S1") (pin "1") (pinfunction "S_1") (pintype "passive"))
    )
    (net (code "116") (name "unconnected-(S1-S1-Pad2)") (class "Default")
      (node (ref "S1") (pin "2") (pinfunction "S1_2") (pintype "passive"))
    )
    (net (code "117") (name "unconnected-(S2-S-Pad1)") (class "Default")
      (node (ref "S2") (pin "1") (pinfunction "S_1") (pintype "passive"))
    )
    (net (code "118") (name "unconnected-(S2-S1-Pad2)") (class "Default")
      (node (ref "S2") (pin "2") (pinfunction "S1_2") (pintype "passive"))
    )
    (net (code "119") (name "unconnected-(S3-S-Pad1)") (class "Default")
      (node (ref "S3") (pin "1") (pinfunction "S_1") (pintype "passive"))
    )
    (net (code "120") (name "unconnected-(S3-S1-Pad2)") (class "Default")
      (node (ref "S3") (pin "2") (pinfunction "S1_2") (pintype "passive"))
    )
    (net (code "121") (name "unconnected-(S4-S-Pad1)") (class "Default")
      (node (ref "S4") (pin "1") (pinfunction "S_1") (pintype "passive"))
    )
    (net (code "122") (name "unconnected-(S4-S1-Pad2)") (class "Default")
      (node (ref "S4") (pin "2") (pinfunction "S1_2") (pintype "passive"))
    )
    (net (code "123") (name "unconnected-(S5-S-Pad1)") (class "Default")
      (node (ref "S5") (pin "1") (pinfunction "S_1") (pintype "passive"))
    )
    (net (code "124") (name "unconnected-(S5-S1-Pad2)") (class "Default")
      (node (ref "S5") (pin "2") (pinfunction "S1_2") (pintype "passive"))
    )
    (net (code "125") (name "unconnected-(S6-S-Pad1)") (class "Default")
      (node (ref "S6") (pin "1") (pinfunction "S_1") (pintype "passive"))
    )
    (net (code "126") (name "unconnected-(S6-S1-Pad2)") (class "Default")
      (node (ref "S6") (pin "2") (pinfunction "S1_2") (pintype "passive"))
    )
    (net (code "127") (name "unconnected-(S7-S-Pad1)") (class "Default")
      (node (ref "S7") (pin "1") (pinfunction "S_1") (pintype "passive"))
    )
    (net (code "128") (name "unconnected-(S7-S1-Pad2)") (class "Default")
      (node (ref "S7") (pin "2") (pinfunction "S1_2") (pintype "passive"))
    )
    (net (code "129") (name "unconnected-(S8-S-Pad1)") (class "Default")
      (node (ref "S8") (pin "1") (pinfunction "S_1") (pintype "passive"))
    )
    (net (code "130") (name "unconnected-(S8-S1-Pad2)") (class "Default")
      (node (ref "S8") (pin "2") (pinfunction "S1_2") (pintype "passive"))
    )
    (net (code "131") (name "unconnected-(X2D-S-Pad4)") (class "Default")
      (node (ref "X2") (pin "4") (pinfunction "S_4") (pintype "passive"))
    )
    (net (code "132") (name "unconnected-(X3A-S-Pad1)") (class "Default")
      (node (ref "X3") (pin "1") (pinfunction "S_1") (pintype "passive"))
    )
  )
)
